# ESQUEMATICO.net
KiCad netlist of a schematic drawn in Altium Designer
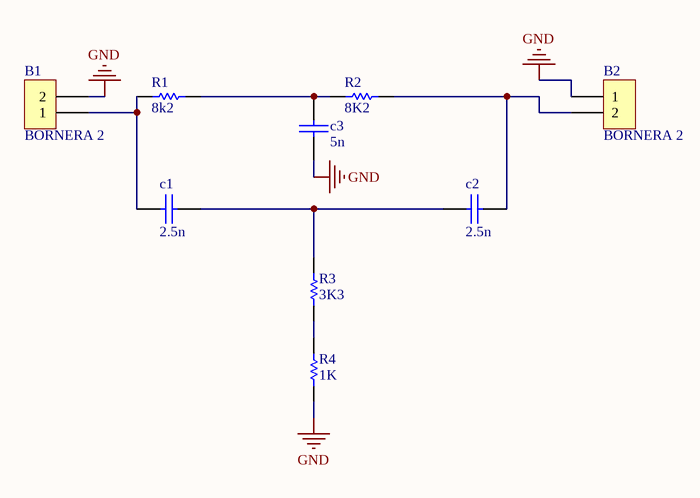
[diagram p0: ESQUEMATICO.SchDoc]

(export (version "E")
  (design (tool "Eeschema 10.0.6"))
  (components
    (comp (ref "B1") (value "BORNERA 2") (footprint "BORNERA2") (libsource (lib "") (part "BORNERA 2_1")))
    (comp (ref "B2")
      (value "BORNERA 2")
      (footprint "BORNERA2")
      (libsource (lib "LIBEBAL") (part "BORNERA 2"))
    )
    (comp (ref "c1") (value "2.5n") (footprint "CAP200") (libsource (lib "LIBEBAL") (part "CAP")))
    (comp (ref "c2") (value "2.5n") (footprint "CAP200") (libsource (lib "LIBEBAL") (part "CAP")))
    (comp (ref "c3") (value "5n") (footprint "CAP200") (libsource (lib "LIBEBAL") (part "CAP")))
    (comp (ref "R1") (value "8k2") (footprint "RES400") (libsource (lib "LIBEBAL") (part "RES")))
    (comp (ref "R2") (value "8K2") (footprint "RES400") (libsource (lib "LIBEBAL") (part "RES")))
    (comp (ref "R3") (value "3K3") (footprint "RES400") (libsource (lib "LIBEBAL") (part "RES")))
    (comp (ref "R4") (value "1K") (footprint "RES400") (libsource (lib "LIBEBAL") (part "RES")))
  )
  (nets
    (net (code "1") (name "GND") (class "Default")
      (node (ref "B1") (pin "2") (pinfunction "2_2") (pintype "passive"))
      (node (ref "B2") (pin "1") (pinfunction "1_1") (pintype "passive"))
      (node (ref "R4") (pin "1") (pinfunction "1_1") (pintype "passive"))
      (node (ref "c3") (pin "2") (pinfunction "2_2") (pintype "passive"))
    )
    (net (code "2") (name "Net-(B1-Pad1)") (class "Default")
      (node (ref "B1") (pin "1") (pinfunction "1_1") (pintype "passive"))
      (node (ref "R1") (pin "1") (pinfunction "1_1") (pintype "passive"))
      (node (ref "c1") (pin "1") (pinfunction "1_1") (pintype "passive"))
    )
    (net (code "3") (name "Net-(B2-Pad2)") (class "Default")
      (node (ref "B2") (pin "2") (pinfunction "2_2") (pintype "passive"))
      (node (ref "R2") (pin "2") (pinfunction "2_2") (pintype "passive"))
      (node (ref "c2") (pin "2") (pinfunction "2_2") (pintype "passive"))
    )
    (net (code "4") (name "Net-(R1-Pad2)") (class "Default")
      (node (ref "R1") (pin "2") (pinfunction "2_2") (pintype "passive"))
      (node (ref "R2") (pin "1") (pinfunction "1_1") (pintype "passive"))
      (node (ref "c3") (pin "1") (pinfunction "1_1") (pintype "passive"))
    )
    (net (code "5") (name "Net-(R3-Pad1)") (class "Default")
      (node (ref "R3") (pin "1") (pinfunction "1_1") (pintype "passive"))
      (node (ref "R4") (pin "2") (pinfunction "2_2") (pintype "passive"))
    )
    (net (code "6") (name "Net-(R3-Pad2)") (class "Default")
      (node (ref "R3") (pin "2") (pinfunction "2_2") (pintype "passive"))
      (node (ref "c1") (pin "2") (pinfunction "2_2") (pintype "passive"))
      (node (ref "c2") (pin "1") (pinfunction "1_1") (pintype "passive"))
    )
  )
)
